# POWER.net
KiCad netlist of a schematic drawn in Altium Designer
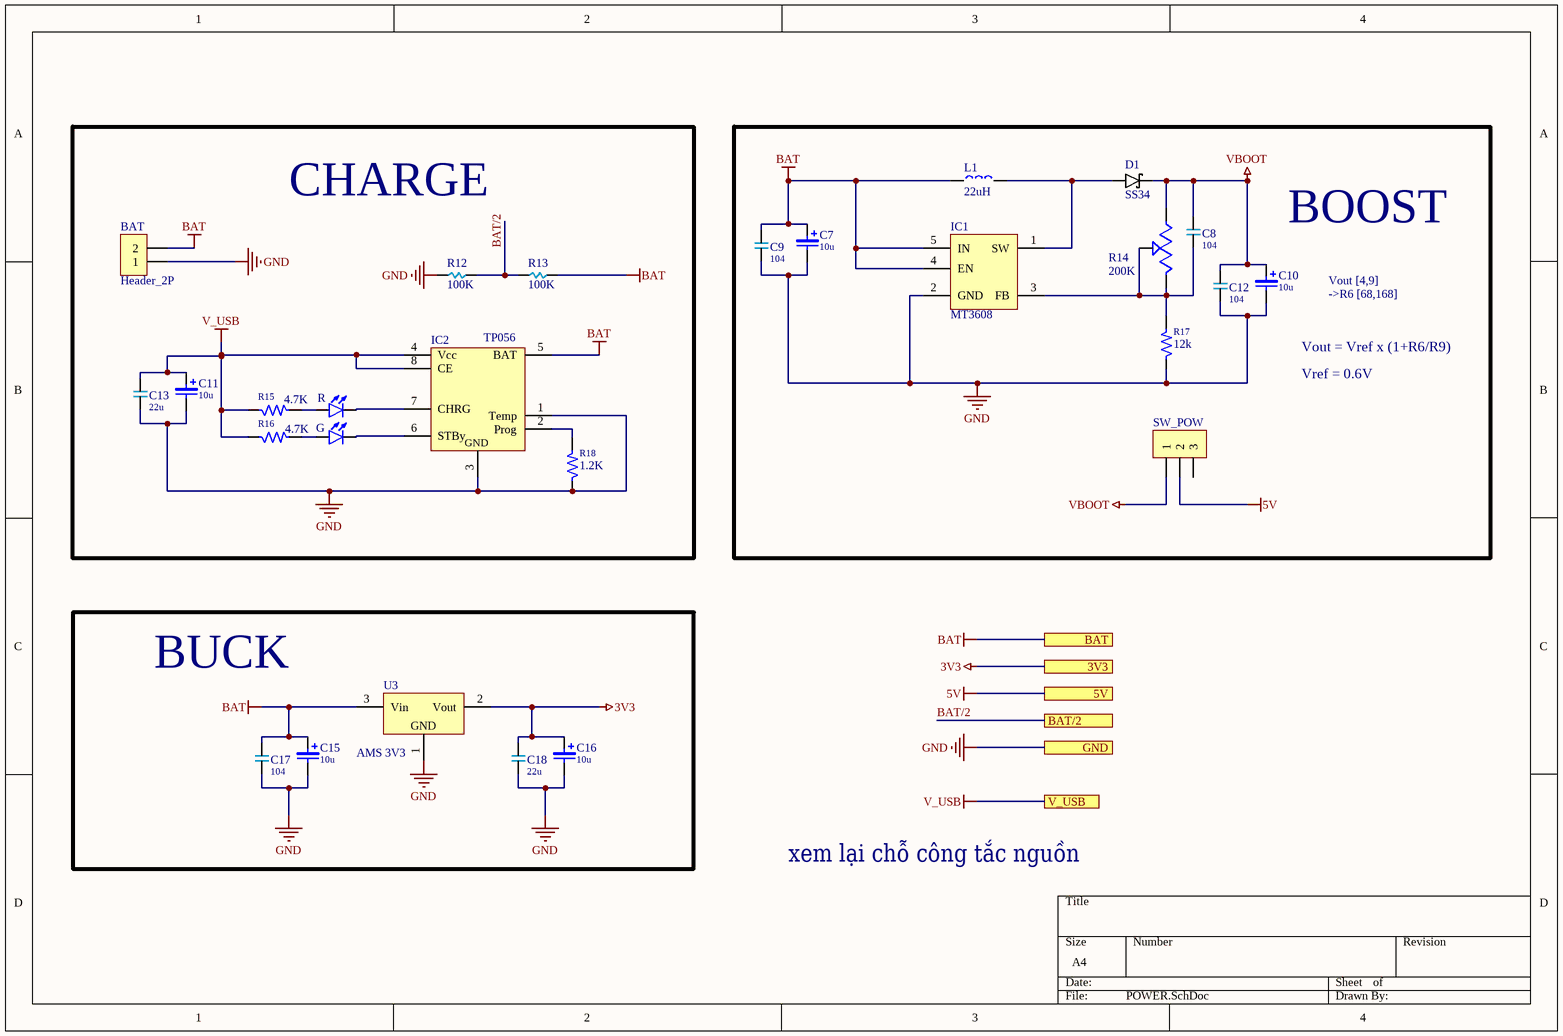
[diagram p0: POWER.SchDoc]

(export (version "E")
  (design (tool "Eeschema 10.0.6"))
  (components
    (comp (ref "BAT")
      (value "Header_2P")
      (footprint "2P_1.5_V")
      (libsource (lib "KM_ALTIUM") (part "Header_2P"))
    )
    (comp (ref "C7")
      (value "10u")
      (footprint "CAP_T 3216 (1208)")
      (libsource (lib "KM_ALTIUM") (part "CAP_T"))
    )
    (comp (ref "C8") (value "104") (footprint "CAP 0603") (libsource (lib "KM_ALTIUM") (part "CAP")))
    (comp (ref "C9") (value "104") (footprint "CAP 0603") (libsource (lib "KM_ALTIUM") (part "CAP")))
    (comp (ref "C10")
      (value "10u")
      (footprint "CAP_T 3216 (1208)")
      (libsource (lib "KM_ALTIUM") (part "CAP_T"))
    )
    (comp (ref "C11")
      (value "10u")
      (footprint "CAP_T 3216 (1208)")
      (libsource (lib "KM_ALTIUM") (part "CAP_T"))
    )
    (comp (ref "C12") (value "104") (footprint "CAP 0603") (libsource (lib "KM_ALTIUM") (part "CAP")))
    (comp (ref "C13") (value "22u") (footprint "CAP 0603") (libsource (lib "KM_ALTIUM") (part "CAP")))
    (comp (ref "C15")
      (value "10u")
      (footprint "CAP_T 3216 (1208)")
      (libsource (lib "KM_ALTIUM") (part "CAP_T"))
    )
    (comp (ref "C16")
      (value "10u")
      (footprint "CAP_T 3216 (1208)")
      (libsource (lib "KM_ALTIUM") (part "CAP_T"))
    )
    (comp (ref "C17") (value "104") (footprint "CAP 0603") (libsource (lib "KM_ALTIUM") (part "CAP")))
    (comp (ref "C18") (value "22u") (footprint "CAP 0603") (libsource (lib "KM_ALTIUM") (part "CAP")))
    (comp (ref "D1") (value "SS34") (footprint "DO214AC-SMA") (libsource (lib "KM_ALTIUM") (part "DIODE S")))
    (comp (ref "G") (value "Green") (footprint "LED 0603") (libsource (lib "KM_ALTIUM") (part "LED SM")))
    (comp (ref "IC1") (value "MT3608") (footprint "SOT23-6") (libsource (lib "KM_ALTIUM") (part "MT3608")))
    (comp (ref "IC2") (value "TP056") (footprint "SOIC 8") (libsource (lib "KM_ALTIUM") (part "TP4056")))
    (comp (ref "L1") (value "22uH") (footprint "INDUCTOR 0630") (libsource (lib "KM_ALTIUM") (part "IDT")))
    (comp (ref "R") (value "Green") (footprint "LED 0603") (libsource (lib "KM_ALTIUM") (part "LED SM")))
    (comp (ref "R12") (value "100K") (footprint "RES 0603") (libsource (lib "KM_ALTIUM") (part "RES")))
    (comp (ref "R13") (value "100K") (footprint "RES 0603") (libsource (lib "KM_ALTIUM") (part "RES")))
    (comp (ref "R14")
      (value "200K")
      (footprint "RES VARIABLE")
      (description "SMD")
      (libsource (lib "KM_ALTIUM") (part "Res_variable"))
    )
    (comp (ref "R15")
      (value "4.7K")
      (footprint "RES 0603")
      (description "Res 0805")
      (libsource (lib "KM_ALTIUM") (part "Res SMD"))
    )
    (comp (ref "R16")
      (value "4.7K")
      (footprint "RES 0603")
      (description "Res 0805")
      (libsource (lib "KM_ALTIUM") (part "Res SMD"))
    )
    (comp (ref "R17")
      (value "12k")
      (footprint "RES 0603")
      (description "Res 0805")
      (libsource (lib "KM_ALTIUM") (part "Res SMD"))
    )
    (comp (ref "R18")
      (value "1.2K")
      (footprint "RES 0603")
      (description "Res 0805")
      (libsource (lib "KM_ALTIUM") (part "Res SMD"))
    )
    (comp (ref "SW_POW")
      (value "SWITCH")
      (footprint "Switch SK12D07")
      (libsource (lib "KM_ALTIUM") (part "SWITCH"))
    )
    (comp (ref "U3") (value "AMS 3V3") (footprint "SOT223") (libsource (lib "KM_ALTIUM") (part "AMS1117")))
  )
  (nets
    (net (code "1") (name "/BAT{slash}2") (class "Default")
      (node (ref "R12") (pin "1") (pinfunction "1_1") (pintype "passive"))
      (node (ref "R13") (pin "2") (pinfunction "2_2") (pintype "passive"))
    )
    (net (code "2") (name "3V3") (class "Default")
      (node (ref "C16") (pin "1") (pinfunction "1_1") (pintype "passive"))
      (node (ref "C18") (pin "2") (pinfunction "2_2") (pintype "passive"))
      (node (ref "U3") (pin "2") (pinfunction "Vout_2") (pintype "passive"))
    )
    (net (code "3") (name "5V") (class "Default")
      (node (ref "SW_POW") (pin "2") (pinfunction "2_2") (pintype "passive"))
    )
    (net (code "4") (name "BAT") (class "Default")
      (node (ref "BAT") (pin "2") (pinfunction "2_2") (pintype "passive"))
      (node (ref "C15") (pin "1") (pinfunction "1_1") (pintype "passive"))
      (node (ref "C17") (pin "2") (pinfunction "2_2") (pintype "passive"))
      (node (ref "C7") (pin "1") (pinfunction "1_1") (pintype "passive"))
      (node (ref "C9") (pin "2") (pinfunction "2_2") (pintype "passive"))
      (node (ref "IC1") (pin "4") (pinfunction "EN_4") (pintype "passive"))
      (node (ref "IC1") (pin "5") (pinfunction "IN_5") (pintype "passive"))
      (node (ref "IC2") (pin "5") (pinfunction "BAT_5") (pintype "passive"))
      (node (ref "L1") (pin "1") (pinfunction "1_1") (pintype "passive"))
      (node (ref "R13") (pin "1") (pinfunction "1_1") (pintype "passive"))
      (node (ref "U3") (pin "3") (pinfunction "Vin_3") (pintype "passive"))
    )
    (net (code "5") (name "GND") (class "Default")
      (node (ref "BAT") (pin "1") (pinfunction "1_1") (pintype "passive"))
      (node (ref "C10") (pin "2") (pinfunction "2_2") (pintype "passive"))
      (node (ref "C11") (pin "2") (pinfunction "2_2") (pintype "passive"))
      (node (ref "C12") (pin "1") (pinfunction "1_1") (pintype "passive"))
      (node (ref "C13") (pin "1") (pinfunction "1_1") (pintype "passive"))
      (node (ref "C15") (pin "2") (pinfunction "2_2") (pintype "passive"))
      (node (ref "C16") (pin "2") (pinfunction "2_2") (pintype "passive"))
      (node (ref "C17") (pin "1") (pinfunction "1_1") (pintype "passive"))
      (node (ref "C18") (pin "1") (pinfunction "1_1") (pintype "passive"))
      (node (ref "C7") (pin "2") (pinfunction "2_2") (pintype "passive"))
      (node (ref "C9") (pin "1") (pinfunction "1_1") (pintype "passive"))
      (node (ref "IC1") (pin "2") (pinfunction "GND_2") (pintype "passive"))
      (node (ref "IC2") (pin "1") (pinfunction "Temp_1") (pintype "passive"))
      (node (ref "IC2") (pin "3") (pinfunction "Gnd_3") (pintype "passive"))
      (node (ref "R12") (pin "2") (pinfunction "2_2") (pintype "passive"))
      (node (ref "R17") (pin "1") (pinfunction "1_1") (pintype "passive"))
      (node (ref "R18") (pin "1") (pinfunction "1_1") (pintype "passive"))
      (node (ref "U3") (pin "1") (pinfunction "gnd_1") (pintype "passive"))
    )
    (net (code "6") (name "Net-(G-PadA)") (class "Default")
      (node (ref "G") (pin "A") (pinfunction "A_A") (pintype "passive"))
      (node (ref "R16") (pin "2") (pinfunction "2_2") (pintype "passive"))
    )
    (net (code "7") (name "Net-(IC1-FB)") (class "Default")
      (node (ref "C8") (pin "1") (pinfunction "1_1") (pintype "passive"))
      (node (ref "IC1") (pin "3") (pinfunction "FB_3") (pintype "passive"))
      (node (ref "R14") (pin "2") (pinfunction "2_2") (pintype "passive"))
      (node (ref "R14") (pin "3") (pinfunction "3_3") (pintype "passive"))
      (node (ref "R17") (pin "2") (pinfunction "2_2") (pintype "passive"))
    )
    (net (code "8") (name "Net-(IC1-SW)") (class "Default")
      (node (ref "D1") (pin "A") (pinfunction "A_A") (pintype "passive"))
      (node (ref "IC1") (pin "1") (pinfunction "SW_1") (pintype "passive"))
      (node (ref "L1") (pin "2") (pinfunction "2_2") (pintype "passive"))
    )
    (net (code "9") (name "Net-(IC2-CHRG)") (class "Default")
      (node (ref "IC2") (pin "7") (pinfunction "CHRG_7") (pintype "passive"))
      (node (ref "R") (pin "K") (pinfunction "K_K") (pintype "passive"))
    )
    (net (code "10") (name "Net-(IC2-Prog)") (class "Default")
      (node (ref "IC2") (pin "2") (pinfunction "Prog_2") (pintype "passive"))
      (node (ref "R18") (pin "2") (pinfunction "2_2") (pintype "passive"))
    )
    (net (code "11") (name "Net-(IC2-STBy)") (class "Default")
      (node (ref "G") (pin "K") (pinfunction "K_K") (pintype "passive"))
      (node (ref "IC2") (pin "6") (pinfunction "STBy_6") (pintype "passive"))
    )
    (net (code "12") (name "Net-(R-PadA)") (class "Default")
      (node (ref "R") (pin "A") (pinfunction "A_A") (pintype "passive"))
      (node (ref "R15") (pin "2") (pinfunction "2_2") (pintype "passive"))
    )
    (net (code "13") (name "VBOOT") (class "Default")
      (node (ref "C10") (pin "1") (pinfunction "1_1") (pintype "passive"))
      (node (ref "C12") (pin "2") (pinfunction "2_2") (pintype "passive"))
      (node (ref "C8") (pin "2") (pinfunction "2_2") (pintype "passive"))
      (node (ref "D1") (pin "K") (pinfunction "K_K") (pintype "passive"))
      (node (ref "R14") (pin "1") (pinfunction "1_1") (pintype "passive"))
      (node (ref "SW_POW") (pin "1") (pinfunction "1_1") (pintype "passive"))
    )
    (net (code "14") (name "V_USB") (class "Default")
      (node (ref "C11") (pin "1") (pinfunction "1_1") (pintype "passive"))
      (node (ref "C13") (pin "2") (pinfunction "2_2") (pintype "passive"))
      (node (ref "IC2") (pin "4") (pinfunction "Vcc_4") (pintype "passive"))
      (node (ref "IC2") (pin "8") (pinfunction "CE_8") (pintype "passive"))
      (node (ref "R15") (pin "1") (pinfunction "1_1") (pintype "passive"))
      (node (ref "R16") (pin "1") (pinfunction "1_1") (pintype "passive"))
    )
    (net (code "15") (name "unconnected-(SW_POW-Pad3)") (class "Default")
      (node (ref "SW_POW") (pin "3") (pinfunction "3_3") (pintype "passive"))
    )
  )
)
